# ICM-42605-breakout.net
KiCad netlist of a schematic drawn in EAGLE
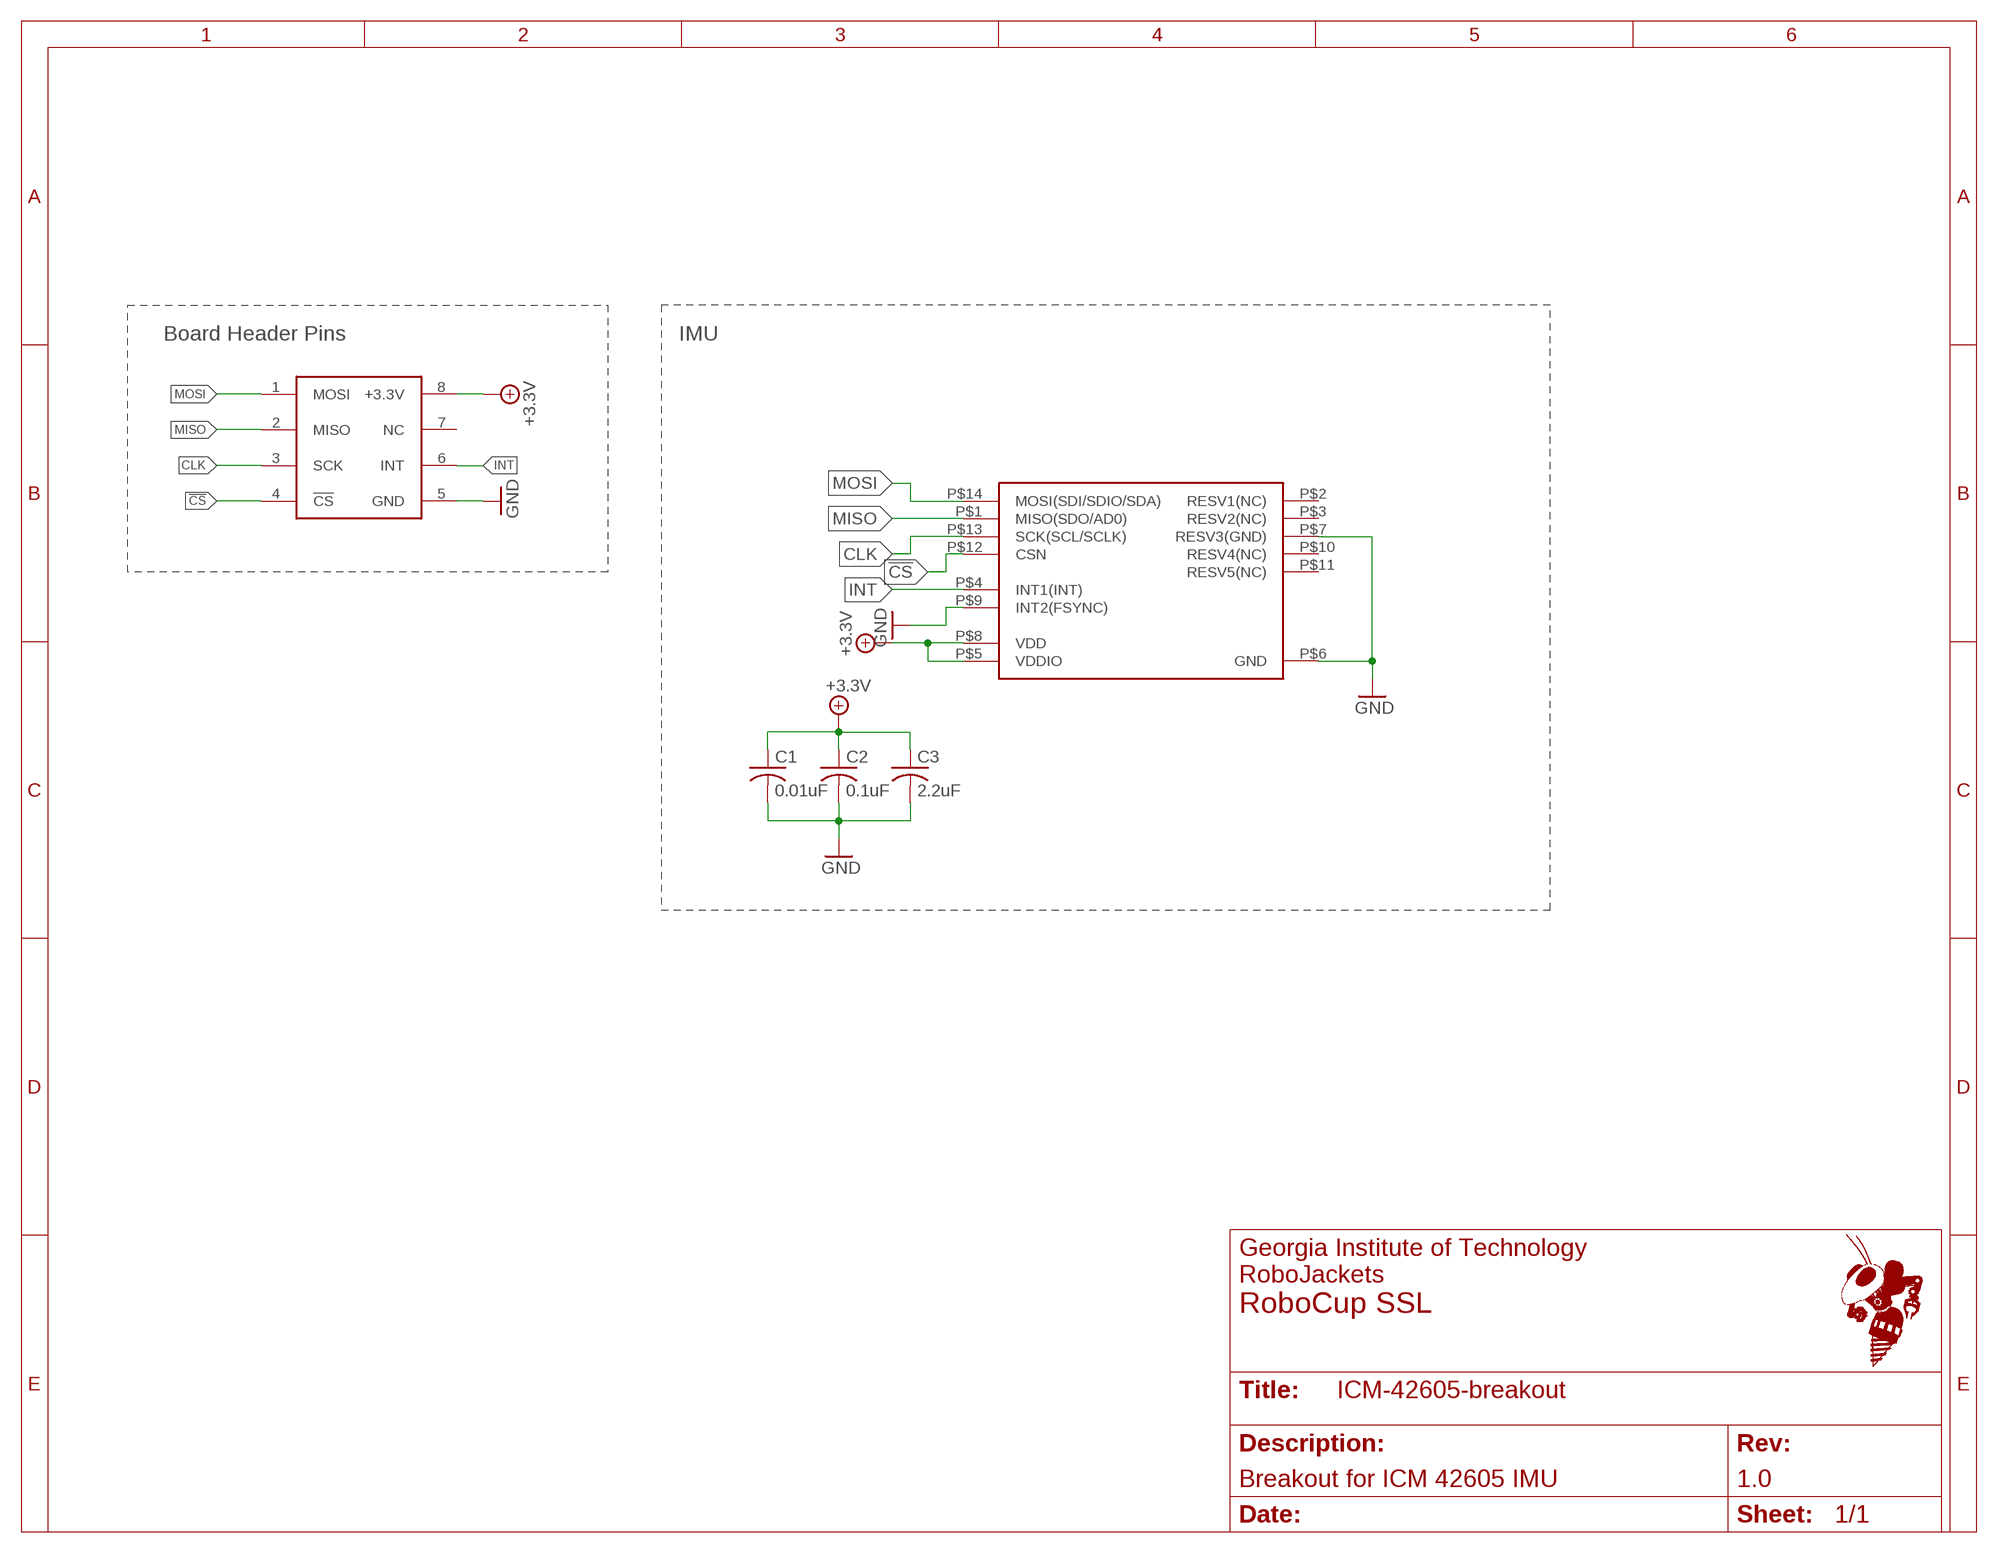
[diagram p0: schematic, sheet 1]

(export (version "E")
  (design (tool "Eeschema 10.0.6"))
  (components
    (comp (ref "C1")
      (value "0.01uF")
      (footprint "eagle-import:C0603")
      (libsource (lib "eagle-import") (part "C-USC0603"))
    )
    (comp (ref "C2")
      (value "0.1uF")
      (footprint "eagle-import:C0603")
      (libsource (lib "eagle-import") (part "C-USC0603"))
    )
    (comp (ref "C3")
      (value "2.2uF")
      (footprint "eagle-import:C0603")
      (libsource (lib "eagle-import") (part "C-USC0603"))
    )
    (comp (ref "KIT1")
      (value "IMUIMU-KIT")
      (footprint "eagle-import:IMU-KIT")
      (libsource (lib "eagle-import") (part "IMUIMU-KIT"))
    )
    (comp (ref "U3")
      (value "ICM-42605")
      (footprint "eagle-import:ICM-442605-2530091")
      (fields (field (name "MANUFACTURER") "InvenSense"))
      (libsource (lib "eagle-import") (part "ICM-42605"))
    )
  )
  (nets
    (net (code "1") (name "+3.3V") (class "Default")
      (node (ref "C1") (pin "1") (pinfunction "1_1") (pintype "passive"))
      (node (ref "C2") (pin "1") (pinfunction "1_1") (pintype "passive"))
      (node (ref "C3") (pin "1") (pinfunction "1_1") (pintype "passive"))
      (node (ref "KIT1") (pin "8") (pinfunction "+3.3V_8") (pintype "bidirectional"))
      (node (ref "U3") (pin "P$5") (pinfunction "VDDIO_P$5") (pintype "bidirectional"))
      (node (ref "U3") (pin "P$8") (pinfunction "VDD_P$8") (pintype "bidirectional"))
    )
    (net (code "2") (name "/~{CS}") (class "Default")
      (node (ref "KIT1") (pin "4") (pinfunction "~{CS}_4") (pintype "bidirectional"))
      (node (ref "U3") (pin "P$12") (pinfunction "CSN_P$12") (pintype "bidirectional"))
    )
    (net (code "3") (name "CLK") (class "Default")
      (node (ref "KIT1") (pin "3") (pinfunction "SCK_3") (pintype "bidirectional"))
      (node (ref "U3") (pin "P$13") (pinfunction "SCK(SCL/SCLK)_P$13") (pintype "bidirectional"))
    )
    (net (code "4") (name "GND") (class "Default")
      (node (ref "C1") (pin "2") (pinfunction "2_2") (pintype "passive"))
      (node (ref "C2") (pin "2") (pinfunction "2_2") (pintype "passive"))
      (node (ref "C3") (pin "2") (pinfunction "2_2") (pintype "passive"))
      (node (ref "KIT1") (pin "5") (pinfunction "GND_5") (pintype "bidirectional"))
      (node (ref "U3") (pin "P$6") (pinfunction "GND_P$6") (pintype "bidirectional"))
      (node (ref "U3") (pin "P$7") (pinfunction "RESV3(GND)_P$7") (pintype "bidirectional"))
      (node (ref "U3") (pin "P$9") (pinfunction "INT2(FSYNC)_P$9") (pintype "bidirectional"))
    )
    (net (code "5") (name "INT") (class "Default")
      (node (ref "KIT1") (pin "6") (pinfunction "INT_6") (pintype "bidirectional"))
      (node (ref "U3") (pin "P$4") (pinfunction "INT1(INT)_P$4") (pintype "bidirectional"))
    )
    (net (code "6") (name "MISO") (class "Default")
      (node (ref "KIT1") (pin "2") (pinfunction "MISO_2") (pintype "bidirectional"))
      (node (ref "U3") (pin "P$1") (pinfunction "MISO(SDO/AD0)_P$1") (pintype "bidirectional"))
    )
    (net (code "7") (name "MOSI") (class "Default")
      (node (ref "KIT1") (pin "1") (pinfunction "MOSI_1") (pintype "bidirectional"))
      (node (ref "U3") (pin "P$14") (pinfunction "MOSI(SDI/SDIO/SDA)_P$14") (pintype "bidirectional"))
    )
    (net (code "8") (name "unconnected-(KIT1-NC-Pad7)") (class "Default")
      (node (ref "KIT1") (pin "7") (pinfunction "NC_7") (pintype "bidirectional"))
    )
    (net (code "9") (name "unconnected-(U3-RESV1(NC)-PadP$2)") (class "Default")
      (node (ref "U3") (pin "P$2") (pinfunction "RESV1(NC)_P$2") (pintype "bidirectional"))
    )
    (net (code "10") (name "unconnected-(U3-RESV2(NC)-PadP$3)") (class "Default")
      (node (ref "U3") (pin "P$3") (pinfunction "RESV2(NC)_P$3") (pintype "bidirectional"))
    )
    (net (code "11") (name "unconnected-(U3-RESV4(NC)-PadP$10)") (class "Default")
      (node (ref "U3") (pin "P$10") (pinfunction "RESV4(NC)_P$10") (pintype "bidirectional"))
    )
    (net (code "12") (name "unconnected-(U3-RESV5(NC)-PadP$11)") (class "Default")
      (node (ref "U3") (pin "P$11") (pinfunction "RESV5(NC)_P$11") (pintype "bidirectional"))
    )
  )
)
